# FDC1004DGST.net
KiCad netlist of a schematic drawn in Altium Designer
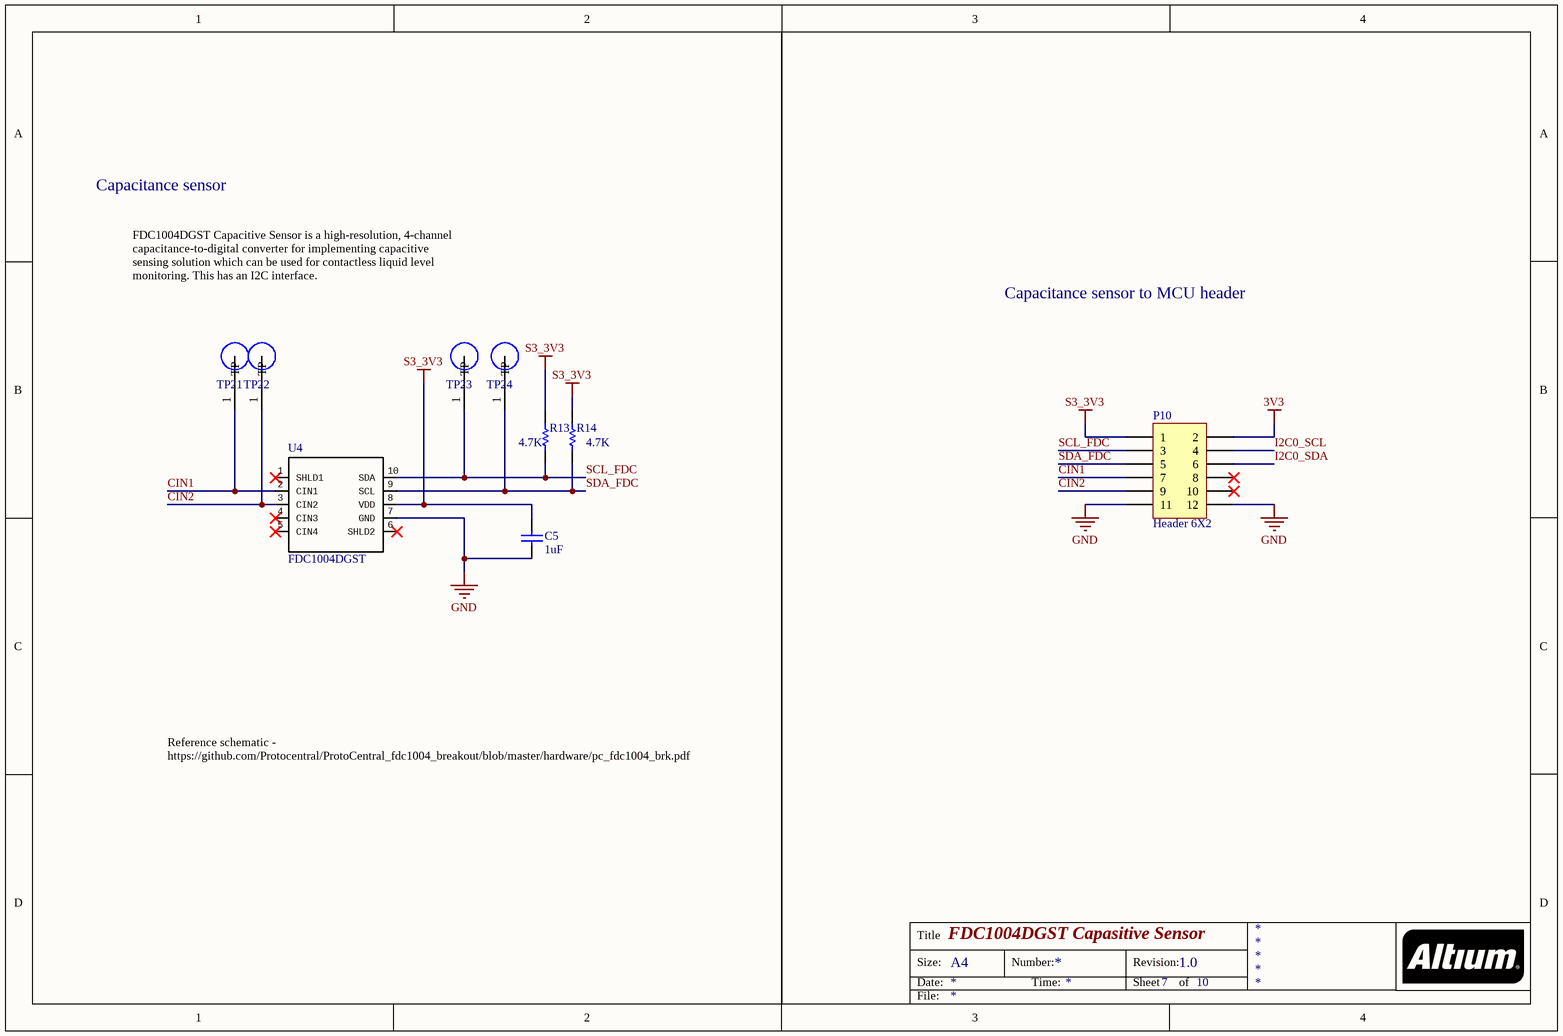
[diagram p0: FDC1004DGST.SchDoc]

(export (version "E")
  (design (tool "Eeschema 10.0.6"))
  (components
    (comp (ref "C5")
      (value "1uF")
      (footprint "1608[0603]")
      (description "Capacitor")
      (fields
        (field (name "DIGI-KEY PART NUMBER") "1276-6524-1-ND")
        (field (name "MANUFACTURER") "Samsung Electro-Mechanics")
      )
      (libsource (lib "Miscellaneous Devices") (part "Cap"))
    )
    (comp (ref "P10")
      (value "Header 6X2")
      (footprint "HDR2X6")
      (description "Header, 6-Pin, Dual row")
      (fields
        (field (name "DIGI-KEY PART NUMBER") "609-3237-ND")
        (field (name "MANUFACTURER PART NUMBER") "67997-212HLF")
      )
      (libsource (lib "Miscellaneous Connectors") (part "Header 6X2"))
    )
    (comp (ref "R13")
      (value "4.7K")
      (footprint "1608[0603]")
      (description "RES SMD 4.7K OHM 5% 1/10W 0603")
      (fields (field (name "DIGI-KEY PART NUMBER") "311-4.7KGRCT-ND") (field (name "MANUFACTURER") "Yageo"))
      (libsource (lib "Miscellaneous Devices") (part "Res1"))
    )
    (comp (ref "R14")
      (value "4.7K")
      (footprint "1608[0603]")
      (description "RES SMD 4.7K OHM 5% 1/10W 0603")
      (fields (field (name "DIGI-KEY PART NUMBER") "311-4.7KGRCT-ND") (field (name "MANUFACTURER") "Yageo"))
      (libsource (lib "Miscellaneous Devices") (part "Res1"))
    )
    (comp (ref "TP21")
      (value "TP")
      (footprint "TP")
      (description "PC TEST POINT MINIATURE")
      (fields
        (field (name "MANUFACTURER") "Keystone Electronics")
        (field (name "DIGI-KEY PART NUMBER") "36-5019CT-ND")
      )
      (libsource (lib "TP") (part "TP"))
    )
    (comp (ref "TP22")
      (value "TP")
      (footprint "TP")
      (description "PC TEST POINT MINIATURE")
      (fields
        (field (name "MANUFACTURER") "Keystone Electronics")
        (field (name "DIGI-KEY PART NUMBER") "36-5019CT-ND")
      )
      (libsource (lib "TP") (part "TP"))
    )
    (comp (ref "TP23")
      (value "TP")
      (footprint "TP")
      (description "PC TEST POINT MINIATURE")
      (fields
        (field (name "MANUFACTURER") "Keystone Electronics")
        (field (name "DIGI-KEY PART NUMBER") "36-5019CT-ND")
      )
      (libsource (lib "TP") (part "TP"))
    )
    (comp (ref "TP24")
      (value "TP")
      (footprint "TP")
      (description "PC TEST POINT MINIATURE")
      (fields
        (field (name "MANUFACTURER") "Keystone Electronics")
        (field (name "DIGI-KEY PART NUMBER") "36-5019CT-ND")
      )
      (libsource (lib "TP") (part "TP"))
    )
    (comp (ref "U4")
      (value "FDC1004DGST")
      (footprint "FDC1004DGST")
      (description "CAPACITIVE SENSING SOLUTIONS")
      (fields
        (field (name "DIGI-KEY PART NUMBER") "296-49639-1-ND")
        (field (name "MANUFACTURER") "Texas Instruments")
      )
      (libsource (lib "Hydrated_Buffs") (part "FDC1004DGST"))
    )
  )
  (nets
    (net (code "1") (name "/CIN1") (class "Default")
      (node (ref "P10") (pin "7") (pinfunction "7_7") (pintype "passive"))
      (node (ref "TP21") (pin "1") (pinfunction "TP_1") (pintype "passive"))
      (node (ref "U4") (pin "2") (pinfunction "CIN1_2") (pintype "passive"))
    )
    (net (code "2") (name "/CIN2") (class "Default")
      (node (ref "P10") (pin "9") (pinfunction "9_9") (pintype "passive"))
      (node (ref "TP22") (pin "1") (pinfunction "TP_1") (pintype "passive"))
      (node (ref "U4") (pin "3") (pinfunction "CIN2_3") (pintype "passive"))
    )
    (net (code "3") (name "/I2C0_SCL") (class "Default")
      (node (ref "P10") (pin "4") (pinfunction "4_4") (pintype "passive"))
    )
    (net (code "4") (name "/I2C0_SDA") (class "Default")
      (node (ref "P10") (pin "6") (pinfunction "6_6") (pintype "passive"))
    )
    (net (code "5") (name "/SCL_FDC") (class "Default")
      (node (ref "P10") (pin "3") (pinfunction "3_3") (pintype "passive"))
      (node (ref "R13") (pin "1") (pinfunction "1_1") (pintype "passive"))
      (node (ref "TP23") (pin "1") (pinfunction "TP_1") (pintype "passive"))
      (node (ref "U4") (pin "10") (pinfunction "SDA_10") (pintype "passive"))
    )
    (net (code "6") (name "/SDA_FDC") (class "Default")
      (node (ref "P10") (pin "5") (pinfunction "5_5") (pintype "passive"))
      (node (ref "R14") (pin "1") (pinfunction "1_1") (pintype "passive"))
      (node (ref "TP24") (pin "1") (pinfunction "TP_1") (pintype "passive"))
      (node (ref "U4") (pin "9") (pinfunction "SCL_9") (pintype "passive"))
    )
    (net (code "7") (name "3V3") (class "Default")
      (node (ref "P10") (pin "2") (pinfunction "2_2") (pintype "passive"))
    )
    (net (code "8") (name "GND") (class "Default")
      (node (ref "C5") (pin "1") (pinfunction "1_1") (pintype "passive"))
      (node (ref "P10") (pin "11") (pinfunction "11_11") (pintype "passive"))
      (node (ref "P10") (pin "12") (pinfunction "12_12") (pintype "passive"))
      (node (ref "U4") (pin "7") (pinfunction "GND_7") (pintype "passive"))
    )
    (net (code "9") (name "S3_3V3") (class "Default")
      (node (ref "C5") (pin "2") (pinfunction "2_2") (pintype "passive"))
      (node (ref "P10") (pin "1") (pinfunction "1_1") (pintype "passive"))
      (node (ref "R13") (pin "2") (pinfunction "2_2") (pintype "passive"))
      (node (ref "R14") (pin "2") (pinfunction "2_2") (pintype "passive"))
      (node (ref "U4") (pin "8") (pinfunction "VDD_8") (pintype "passive"))
    )
    (net (code "10") (name "unconnected-(P10-Pad8)") (class "Default")
      (node (ref "P10") (pin "8") (pinfunction "8_8") (pintype "passive+no_connect"))
    )
    (net (code "11") (name "unconnected-(P10-Pad10)") (class "Default")
      (node (ref "P10") (pin "10") (pinfunction "10_10") (pintype "passive+no_connect"))
    )
    (net (code "12") (name "unconnected-(U4-CIN3-Pad4)") (class "Default")
      (node (ref "U4") (pin "4") (pinfunction "CIN3_4") (pintype "passive+no_connect"))
    )
    (net (code "13") (name "unconnected-(U4-CIN4-Pad5)") (class "Default")
      (node (ref "U4") (pin "5") (pinfunction "CIN4_5") (pintype "passive+no_connect"))
    )
    (net (code "14") (name "unconnected-(U4-SHLD1-Pad1)") (class "Default")
      (node (ref "U4") (pin "1") (pinfunction "SHLD1_1") (pintype "passive+no_connect"))
    )
    (net (code "15") (name "unconnected-(U4-SHLD2-Pad6)") (class "Default")
      (node (ref "U4") (pin "6") (pinfunction "SHLD2_6") (pintype "passive+no_connect"))
    )
  )
)
